# 12-POWER-P12V.net
KiCad netlist of a schematic drawn in Altium Designer
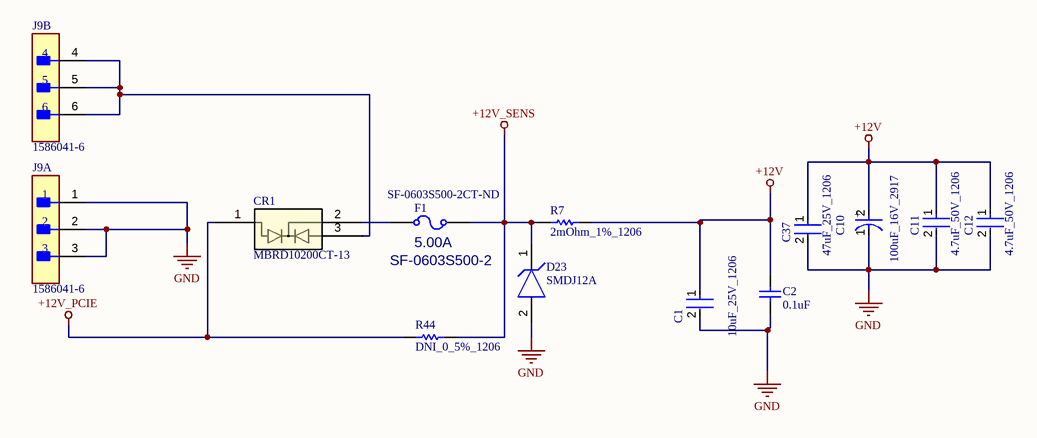
[diagram p0: 12-POWER-P12V.SchDoc]

(export (version "E")
  (design (tool "Eeschema 10.0.6"))
  (components
    (comp (ref "C1")
      (value "10uF_25V_1206")
      (footprint "FP-MK316L-MFG")
      (description "CAP CER 10UF 25V X7R 1206")
      (fields (field (name "TOLERANCE") "10%"))
      (libsource (lib "Altium Content Vault") (part "11868f565c42a9108669ba33697ecf6"))
    )
    (comp (ref "C2")
      (value "0.1uF")
      (footprint "CAPC1608X87X45ML20T05")
      (description "C0603X104K5RACAUTO")
      (fields (field (name "MANUFACTURER") "Kemet"))
      (libsource (lib "Altium Content Vault") (part "CAP"))
    )
    (comp (ref "C10")
      (value "100uF_16V_2917")
      (footprint "FP-T495D107K016ATE125-MFG")
      (description "CAP TANT 100UF 10% 16V 2917")
      (fields (field (name "VOLTAGE") "16V") (field (name "TOLERANCE") "10%"))
      (libsource (lib "Altium Content Vault") (part "a00bbbee19879c290e62620ae7e47b1"))
    )
    (comp (ref "C11")
      (value "4.7uF_50V_1206")
      (footprint "FP-GRM31C-0_2-e0_3_0_8-IPC_C")
      (description "Chip Multilayer Ceramic Capacitors for General Purpose, 1206, 4.7uF, X7R, 15%, 10%, 50V")
      (fields (field (name "VOLTAGE") "50V") (field (name "TOLERANCE") "10%"))
      (libsource (lib "Altium Content Vault") (part "02cd4be3c70576c341d710602a673aa"))
    )
    (comp (ref "C12")
      (value "4.7uF_50V_1206")
      (footprint "FP-GRM31C-0_2-e0_3_0_8-IPC_C")
      (description "Chip Multilayer Ceramic Capacitors for General Purpose, 1206, 4.7uF, X7R, 15%, 10%, 50V")
      (fields (field (name "VOLTAGE") "50V") (field (name "TOLERANCE") "10%"))
      (libsource (lib "Altium Content Vault") (part "02cd4be3c70576c341d710602a673aa"))
    )
    (comp (ref "C37")
      (value "47uF_25V_1206")
      (footprint "FP-C3216-160-0_2-MFG")
      (description "Multilayer Ceramic Capacitors 47uF ±20% 25V X5R SMD 1206")
      (fields (field (name "VOLTAGE") "25V") (field (name "TOLERANCE") "20%"))
      (libsource (lib "Altium Content Vault") (part "11868f565c42a9108669ba33697ecf6"))
    )
    (comp (ref "CR1")
      (value "MBRD10200CT-13")
      (footprint "TO252(DPAK)_DIO")
      (description "No Description Available")
      (libsource (lib "MBRD10200CT-13") (part "MBRD10200CT-13"))
    )
    (comp (ref "D23")
      (value "SMDJ12A")
      (footprint "FP-DO-214AB_SMC_J-Bend-MFG")
      (description "TVS DIODE 12V 19.9V DO214AB")
      (libsource (lib "Altium Content Vault") (part "673ecd2ea4d7fb87b4005b0cb348b7d"))
    )
    (comp (ref "F1")
      (value "5.00A")
      (footprint "FUSM1608X60N")
      (description "FUSE SLOW 5.00A 32V M 0603")
      (fields
        (field (name "MFG PART NUM") "SF-0603S500-2")
        (field (name "VALENTIUM PART NUM") "<VALENTIUM>")
        (field (name "SUPPLIER PART NUMBER 1") "SF-0603S500-2CT-ND")
        (field (name "Comment") "FUSE_0603_5.00A")
      )
      (libsource (lib "Passives") (part "FUSE_0603_2.00A"))
    )
    (comp (ref "J9")
      (value "1586041-6")
      (footprint "FP-1586041-6-MFG")
      (description "CONN HEADER R/A 6POS 4.2MM")
      (fields
        (field (name "OCTOPART") "https://octopart.com/1586041-6-te+connectivity-46514050")
        (field (name "MANUFACTURER") "TE")
      )
      (libsource (lib "Altium Content Vault") (part "bb9cbdb24149a20ba329b4e86909569"))
    )
    (comp (ref "R7")
      (value "2mOhm_1%_1206")
      (footprint "RESC3216X89X64NL25T25")
      (fields (field (name "MANUFACTURER") "Vishay Dale") (field (name "PART NUMBER") "WSL12062L000FEA18"))
      (libsource (lib "Altium Content Vault") (part "RES"))
    )
    (comp (ref "R44")
      (value "DNI_0_5%_1206")
      (footprint "RESC3116X65X50ML20T20")
      (fields (field (name "PART NUMBER") "CRCW12060000Z0EAHP") (field (name "MANUFACTURER") "Vishay Dale"))
      (libsource (lib "Altium Content Vault") (part "RES"))
    )
  )
  (nets
    (net (code "1") (name "+12V") (class "Default")
      (node (ref "C1") (pin "1") (pinfunction "1_1") (pintype "passive"))
      (node (ref "C10") (pin "2") (pinfunction "A_2") (pintype "passive"))
      (node (ref "C11") (pin "1") (pinfunction "1_1") (pintype "passive"))
      (node (ref "C12") (pin "1") (pinfunction "1_1") (pintype "passive"))
      (node (ref "C2") (pin "2") (pinfunction "2_2") (pintype "passive"))
      (node (ref "C37") (pin "1") (pinfunction "1_1") (pintype "passive"))
      (node (ref "R7") (pin "2") (pinfunction "2_2") (pintype "passive"))
    )
    (net (code "2") (name "+12V_PCIE") (class "Default")
      (node (ref "CR1") (pin "1") (pinfunction "1_1") (pintype "passive"))
      (node (ref "R44") (pin "1") (pinfunction "1_1") (pintype "passive"))
    )
    (net (code "3") (name "+12V_SENS") (class "Default")
      (node (ref "D23") (pin "1") (pinfunction "C_1") (pintype "passive"))
      (node (ref "F1") (pin "2") (pinfunction "2_2") (pintype "passive"))
      (node (ref "R44") (pin "2") (pinfunction "2_2") (pintype "passive"))
      (node (ref "R7") (pin "1") (pinfunction "1_1") (pintype "passive"))
    )
    (net (code "4") (name "GND") (class "Default")
      (node (ref "C1") (pin "2") (pinfunction "2_2") (pintype "passive"))
      (node (ref "C10") (pin "1") (pinfunction "C_1") (pintype "passive"))
      (node (ref "C11") (pin "2") (pinfunction "2_2") (pintype "passive"))
      (node (ref "C12") (pin "2") (pinfunction "2_2") (pintype "passive"))
      (node (ref "C2") (pin "1") (pinfunction "1_1") (pintype "passive"))
      (node (ref "C37") (pin "2") (pinfunction "2_2") (pintype "passive"))
      (node (ref "D23") (pin "2") (pinfunction "A_2") (pintype "passive"))
      (node (ref "J9") (pin "1") (pinfunction "1_1") (pintype "passive"))
      (node (ref "J9") (pin "2") (pinfunction "2_2") (pintype "passive"))
      (node (ref "J9") (pin "3") (pinfunction "3_3") (pintype "passive"))
    )
    (net (code "5") (name "Net-(CR1-Pad2)") (class "Default")
      (node (ref "CR1") (pin "2") (pinfunction "2_2") (pintype "passive"))
      (node (ref "F1") (pin "1") (pinfunction "1_1") (pintype "passive"))
    )
    (net (code "6") (name "Net-(CR1-Pad3)") (class "Default")
      (node (ref "CR1") (pin "3") (pinfunction "3_3") (pintype "passive"))
      (node (ref "J9") (pin "4") (pinfunction "4_4") (pintype "passive"))
      (node (ref "J9") (pin "5") (pinfunction "5_5") (pintype "passive"))
      (node (ref "J9") (pin "6") (pinfunction "6_6") (pintype "passive"))
    )
  )
)
